# Sheet2.net
KiCad netlist of a schematic drawn in Altium Designer
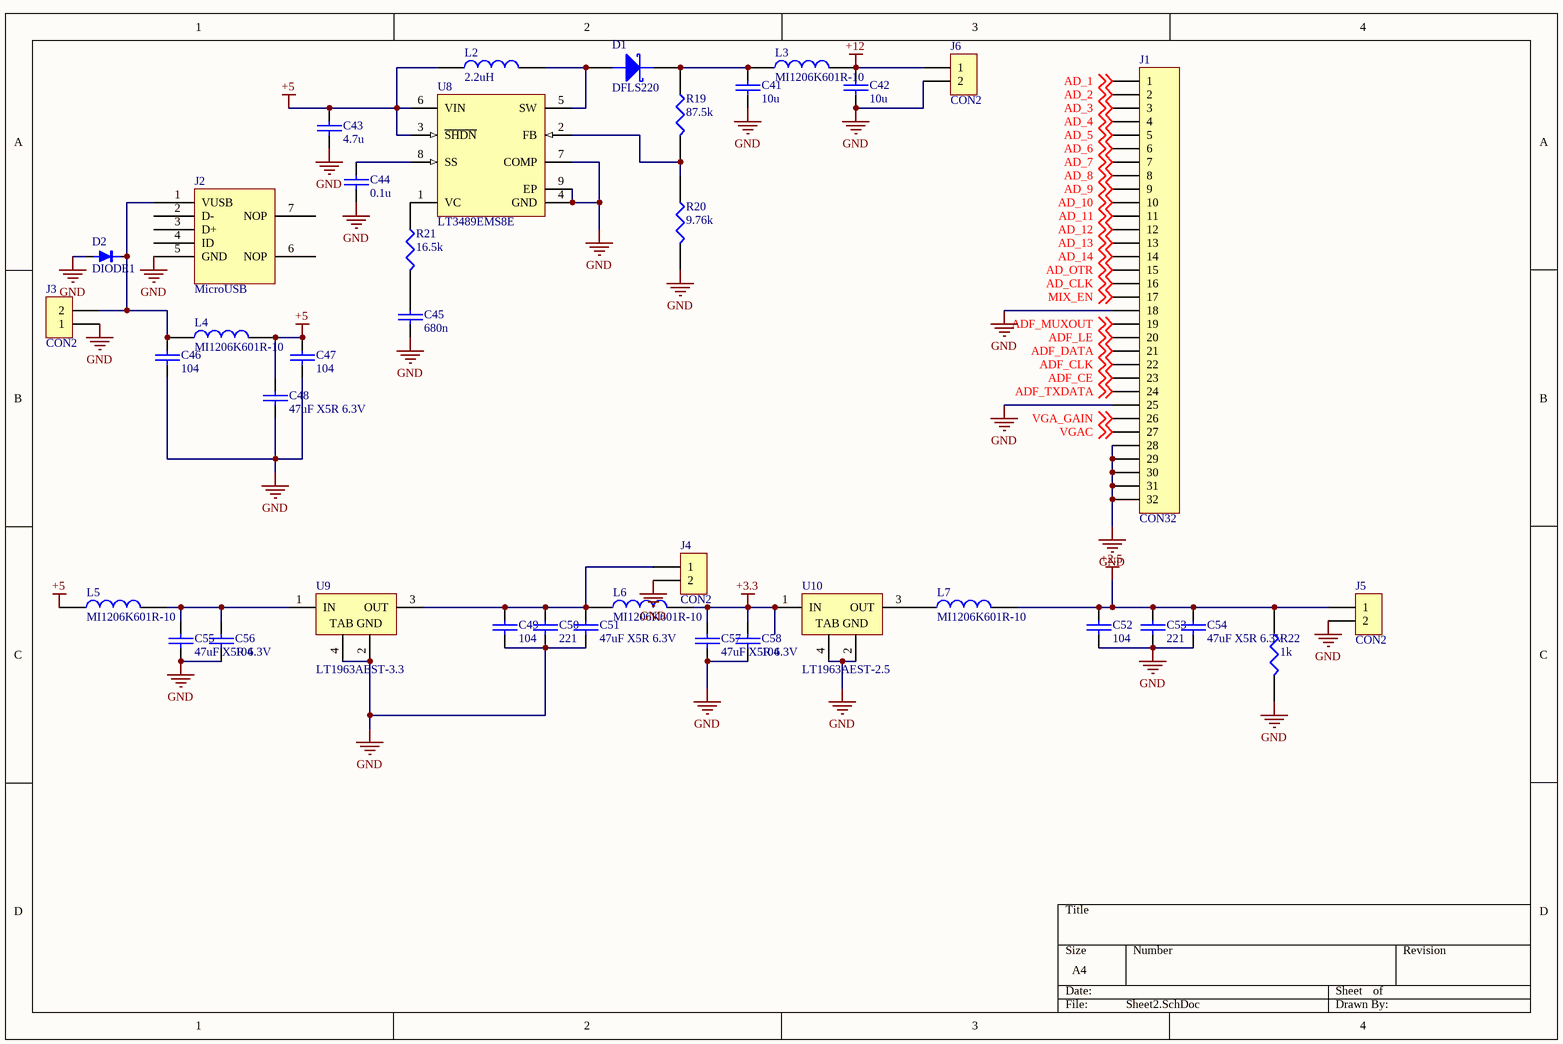
[diagram p0: Sheet2.SchDoc]

(export (version "E")
  (design (tool "Eeschema 10.0.6"))
  (components
    (comp (ref "C41")
      (value "10u")
      (footprint "0603_R")
      (description "Capacitor")
      (libsource (lib "Miscellaneous Devices") (part "CAP"))
    )
    (comp (ref "C42")
      (value "10u")
      (footprint "0603_R")
      (description "Capacitor")
      (libsource (lib "Miscellaneous Devices") (part "CAP"))
    )
    (comp (ref "C43")
      (value "4.7u")
      (footprint "0603_R")
      (description "Capacitor")
      (libsource (lib "Miscellaneous Devices") (part "CAP"))
    )
    (comp (ref "C44")
      (value "0.1u")
      (footprint "0603_R")
      (description "Capacitor")
      (libsource (lib "Miscellaneous Devices") (part "CAP"))
    )
    (comp (ref "C45")
      (value "680n")
      (footprint "0603_R")
      (description "Capacitor")
      (libsource (lib "Miscellaneous Devices") (part "CAP"))
    )
    (comp (ref "C46")
      (value "104")
      (footprint "0603_C")
      (description "Capacitor")
      (libsource (lib "Miscellaneous Devices") (part "CAP"))
    )
    (comp (ref "C47")
      (value "104")
      (footprint "0603_C")
      (description "Capacitor")
      (libsource (lib "Miscellaneous Devices") (part "CAP"))
    )
    (comp (ref "C48")
      (value "47uF X5R 6.3V")
      (footprint "CD2012-0805")
      (description "Capacitor")
      (libsource (lib "Miscellaneous Devices") (part "CAP"))
    )
    (comp (ref "C49")
      (value "104")
      (footprint "0603_R")
      (description "Capacitor")
      (libsource (lib "Miscellaneous Devices") (part "CAP"))
    )
    (comp (ref "C50")
      (value "221")
      (footprint "0603_R")
      (description "Capacitor")
      (libsource (lib "Miscellaneous Devices") (part "CAP"))
    )
    (comp (ref "C51")
      (value "47uF X5R 6.3V")
      (footprint "CD2012-0805")
      (description "Capacitor")
      (libsource (lib "Miscellaneous Devices") (part "CAP"))
    )
    (comp (ref "C52")
      (value "104")
      (footprint "0603_R")
      (description "Capacitor")
      (libsource (lib "Miscellaneous Devices") (part "CAP"))
    )
    (comp (ref "C53")
      (value "221")
      (footprint "0603_R")
      (description "Capacitor")
      (libsource (lib "Miscellaneous Devices") (part "CAP"))
    )
    (comp (ref "C54")
      (value "47uF X5R 6.3V")
      (footprint "CD2012-0805")
      (description "Capacitor")
      (libsource (lib "Miscellaneous Devices") (part "CAP"))
    )
    (comp (ref "C55")
      (value "47uF X5R 6.3V")
      (footprint "CD2012-0805")
      (description "Capacitor")
      (libsource (lib "Miscellaneous Devices") (part "CAP"))
    )
    (comp (ref "C56")
      (value "104")
      (footprint "0603_R")
      (description "Capacitor")
      (libsource (lib "Miscellaneous Devices") (part "CAP"))
    )
    (comp (ref "C57")
      (value "47uF X5R 6.3V")
      (footprint "CD2012-0805")
      (description "Capacitor")
      (libsource (lib "Miscellaneous Devices") (part "CAP"))
    )
    (comp (ref "C58")
      (value "104")
      (footprint "0603_R")
      (description "Capacitor")
      (libsource (lib "Miscellaneous Devices") (part "CAP"))
    )
    (comp (ref "D1")
      (value "DFLS220")
      (footprint "SOD123")
      (description "Schottky Diode")
      (libsource (lib "Miscellaneous Devices") (part "DIODE SCHOTTKY"))
    )
    (comp (ref "D2") (value "DIODE1") (footprint "DIODE0.4A") (libsource (lib "常用元件库") (part "DIODE1")))
    (comp (ref "J1")
      (value "CON32")
      (footprint "CON32")
      (description "Connector")
      (libsource (lib "Miscellaneous Devices") (part "CON32"))
    )
    (comp (ref "J2") (value "MicroUSB") (footprint "MICRO-USB") (libsource (lib "USB") (part "MicroUSB")))
    (comp (ref "J3") (value "CON2") (footprint "SIP2") (libsource (lib "常用元件库") (part "CON2")))
    (comp (ref "J4") (value "CON2") (footprint "SIP2") (libsource (lib "") (part "CON2_1")))
    (comp (ref "J5") (value "CON2") (footprint "SIP2") (libsource (lib "") (part "CON2_1")))
    (comp (ref "J6") (value "CON2") (footprint "SIP2") (libsource (lib "") (part "CON2_1")))
    (comp (ref "L2")
      (value "2.2uH")
      (footprint "CD4532-1812")
      (libsource (lib "Miscellaneous Devices") (part "INDUCTOR"))
    )
    (comp (ref "L3")
      (value "MI1206K601R-10")
      (footprint "1206")
      (libsource (lib "Miscellaneous Devices") (part "INDUCTOR"))
    )
    (comp (ref "L4")
      (value "MI1206K601R-10")
      (footprint "1206")
      (libsource (lib "Miscellaneous Devices") (part "INDUCTOR"))
    )
    (comp (ref "L5")
      (value "MI1206K601R-10")
      (footprint "1206")
      (libsource (lib "Miscellaneous Devices") (part "INDUCTOR"))
    )
    (comp (ref "L6")
      (value "MI1206K601R-10")
      (footprint "1206")
      (libsource (lib "Miscellaneous Devices") (part "INDUCTOR"))
    )
    (comp (ref "L7")
      (value "MI1206K601R-10")
      (footprint "1206")
      (libsource (lib "Miscellaneous Devices") (part "INDUCTOR"))
    )
    (comp (ref "R19")
      (value "87.5k")
      (footprint "0603_R")
      (libsource (lib "Miscellaneous Devices") (part "RES1"))
    )
    (comp (ref "R20")
      (value "9.76k")
      (footprint "0603_R")
      (libsource (lib "Miscellaneous Devices") (part "RES1"))
    )
    (comp (ref "R21")
      (value "16.5k")
      (footprint "0603_R")
      (libsource (lib "Miscellaneous Devices") (part "RES1"))
    )
    (comp (ref "R22")
      (value "1k")
      (footprint "0603_R")
      (libsource (lib "Miscellaneous Devices") (part "RES1"))
    )
    (comp (ref "U8")
      (value "LT3489EMS8E")
      (footprint "LT-MS8E-8-2060X1830TP_N")
      (description "2 MHz Boost DC/DC Converter with 2.5 A Switch and Soft-Start, 8-pin SOP (MS8E-8), -40 to 85 degC")
      (fields (field (name "MANUFACTURER") "Linear Technology"))
      (libsource (lib "Linear Technology Power Management Switching Regulator LT1074-LT8705") (part "LT3489EMS8E"))
    )
    (comp (ref "U9")
      (value "LT1963AEST-3.3")
      (footprint "LT-ST-3-SOT-223_N")
      (fields (field (name "MANUFACTURER") "Linear Technology"))
      (libsource (lib "Linear Technology Power Management LDO Linear Regulators") (part "LT1963AEST-3.3"))
    )
    (comp (ref "U10")
      (value "LT1963AEST-2.5")
      (footprint "LT-ST-3-SOT-223_N")
      (fields (field (name "MANUFACTURER") "Linear Technology") (field (name "PARTNUMBER") "LT1963AEST-3.3"))
      (libsource (lib "Linear Technology Power Management LDO Linear Regulators") (part "LT1963AEST-3.3"))
    )
  )
  (nets
    (net (code "1") (name "+2.5") (class "Default")
      (node (ref "C52") (pin "1") (pinfunction "1_1") (pintype "passive"))
      (node (ref "C53") (pin "1") (pinfunction "1_1") (pintype "passive"))
      (node (ref "C54") (pin "1") (pinfunction "1_1") (pintype "passive"))
      (node (ref "J5") (pin "1") (pinfunction "1_1") (pintype "passive"))
      (node (ref "L7") (pin "2") (pinfunction "2_2") (pintype "passive"))
      (node (ref "R22") (pin "1") (pinfunction "1_1") (pintype "passive"))
    )
    (net (code "2") (name "+3.3") (class "Default")
      (node (ref "C57") (pin "1") (pinfunction "1_1") (pintype "passive"))
      (node (ref "C58") (pin "1") (pinfunction "1_1") (pintype "passive"))
      (node (ref "L6") (pin "2") (pinfunction "2_2") (pintype "passive"))
      (node (ref "U10") (pin "1") (pinfunction "IN_1") (pintype "power_in"))
    )
    (net (code "3") (name "+5") (class "Default")
      (node (ref "C43") (pin "1") (pinfunction "1_1") (pintype "passive"))
      (node (ref "C47") (pin "1") (pinfunction "1_1") (pintype "passive"))
      (node (ref "C48") (pin "1") (pinfunction "1_1") (pintype "passive"))
      (node (ref "L2") (pin "1") (pinfunction "1_1") (pintype "passive"))
      (node (ref "L4") (pin "2") (pinfunction "2_2") (pintype "passive"))
      (node (ref "L5") (pin "1") (pinfunction "1_1") (pintype "passive"))
      (node (ref "U8") (pin "3") (pinfunction "~{SHDN}_3") (pintype "input"))
      (node (ref "U8") (pin "6") (pinfunction "VIN_6") (pintype "power_in"))
    )
    (net (code "4") (name "+12") (class "Default")
      (node (ref "C42") (pin "1") (pinfunction "1_1") (pintype "passive"))
      (node (ref "J6") (pin "1") (pinfunction "1_1") (pintype "passive"))
      (node (ref "L3") (pin "2") (pinfunction "2_2") (pintype "passive"))
    )
    (net (code "5") (name "ADF_CE") (class "Default")
      (node (ref "J1") (pin "23") (pinfunction "23_23") (pintype "passive"))
    )
    (net (code "6") (name "ADF_CLK") (class "Default")
      (node (ref "J1") (pin "22") (pinfunction "22_22") (pintype "passive"))
    )
    (net (code "7") (name "ADF_DATA") (class "Default")
      (node (ref "J1") (pin "21") (pinfunction "21_21") (pintype "passive"))
    )
    (net (code "8") (name "ADF_LE") (class "Default")
      (node (ref "J1") (pin "20") (pinfunction "20_20") (pintype "passive"))
    )
    (net (code "9") (name "ADF_MUXOUT") (class "Default")
      (node (ref "J1") (pin "19") (pinfunction "19_19") (pintype "passive"))
    )
    (net (code "10") (name "ADF_TXDATA") (class "Default")
      (node (ref "J1") (pin "24") (pinfunction "24_24") (pintype "passive"))
    )
    (net (code "11") (name "AD_1") (class "Default")
      (node (ref "J1") (pin "1") (pinfunction "1_1") (pintype "passive"))
    )
    (net (code "12") (name "AD_2") (class "Default")
      (node (ref "J1") (pin "2") (pinfunction "2_2") (pintype "passive"))
    )
    (net (code "13") (name "AD_3") (class "Default")
      (node (ref "J1") (pin "3") (pinfunction "3_3") (pintype "passive"))
    )
    (net (code "14") (name "AD_4") (class "Default")
      (node (ref "J1") (pin "4") (pinfunction "4_4") (pintype "passive"))
    )
    (net (code "15") (name "AD_5") (class "Default")
      (node (ref "J1") (pin "5") (pinfunction "5_5") (pintype "passive"))
    )
    (net (code "16") (name "AD_6") (class "Default")
      (node (ref "J1") (pin "6") (pinfunction "6_6") (pintype "passive"))
    )
    (net (code "17") (name "AD_7") (class "Default")
      (node (ref "J1") (pin "7") (pinfunction "7_7") (pintype "passive"))
    )
    (net (code "18") (name "AD_8") (class "Default")
      (node (ref "J1") (pin "8") (pinfunction "8_8") (pintype "passive"))
    )
    (net (code "19") (name "AD_9") (class "Default")
      (node (ref "J1") (pin "9") (pinfunction "9_9") (pintype "passive"))
    )
    (net (code "20") (name "AD_10") (class "Default")
      (node (ref "J1") (pin "10") (pinfunction "10_10") (pintype "passive"))
    )
    (net (code "21") (name "AD_11") (class "Default")
      (node (ref "J1") (pin "11") (pinfunction "11_11") (pintype "passive"))
    )
    (net (code "22") (name "AD_12") (class "Default")
      (node (ref "J1") (pin "12") (pinfunction "12_12") (pintype "passive"))
    )
    (net (code "23") (name "AD_13") (class "Default")
      (node (ref "J1") (pin "13") (pinfunction "13_13") (pintype "passive"))
    )
    (net (code "24") (name "AD_14") (class "Default")
      (node (ref "J1") (pin "14") (pinfunction "14_14") (pintype "passive"))
    )
    (net (code "25") (name "AD_CLK") (class "Default")
      (node (ref "J1") (pin "16") (pinfunction "16_16") (pintype "passive"))
    )
    (net (code "26") (name "AD_OTR") (class "Default")
      (node (ref "J1") (pin "15") (pinfunction "15_15") (pintype "passive"))
    )
    (net (code "27") (name "GND") (class "Default")
      (node (ref "C41") (pin "2") (pinfunction "2_2") (pintype "passive"))
      (node (ref "C42") (pin "2") (pinfunction "2_2") (pintype "passive"))
      (node (ref "C43") (pin "2") (pinfunction "2_2") (pintype "passive"))
      (node (ref "C44") (pin "2") (pinfunction "2_2") (pintype "passive"))
      (node (ref "C45") (pin "2") (pinfunction "2_2") (pintype "passive"))
      (node (ref "C46") (pin "2") (pinfunction "2_2") (pintype "passive"))
      (node (ref "C47") (pin "2") (pinfunction "2_2") (pintype "passive"))
      (node (ref "C48") (pin "2") (pinfunction "2_2") (pintype "passive"))
      (node (ref "C49") (pin "2") (pinfunction "2_2") (pintype "passive"))
      (node (ref "C50") (pin "2") (pinfunction "2_2") (pintype "passive"))
      (node (ref "C51") (pin "2") (pinfunction "2_2") (pintype "passive"))
      (node (ref "C52") (pin "2") (pinfunction "2_2") (pintype "passive"))
      (node (ref "C53") (pin "2") (pinfunction "2_2") (pintype "passive"))
      (node (ref "C54") (pin "2") (pinfunction "2_2") (pintype "passive"))
      (node (ref "C55") (pin "2") (pinfunction "2_2") (pintype "passive"))
      (node (ref "C56") (pin "2") (pinfunction "2_2") (pintype "passive"))
      (node (ref "C57") (pin "2") (pinfunction "2_2") (pintype "passive"))
      (node (ref "C58") (pin "2") (pinfunction "2_2") (pintype "passive"))
      (node (ref "D2") (pin "A") (pinfunction "A_A") (pintype "passive"))
      (node (ref "J1") (pin "18") (pinfunction "18_18") (pintype "passive"))
      (node (ref "J1") (pin "25") (pinfunction "25_25") (pintype "passive"))
      (node (ref "J1") (pin "28") (pinfunction "28_28") (pintype "passive"))
      (node (ref "J1") (pin "29") (pinfunction "29_29") (pintype "passive"))
      (node (ref "J1") (pin "30") (pinfunction "30_30") (pintype "passive"))
      (node (ref "J1") (pin "31") (pinfunction "31_31") (pintype "passive"))
      (node (ref "J1") (pin "32") (pinfunction "32_32") (pintype "passive"))
      (node (ref "J2") (pin "5") (pinfunction "GND_5") (pintype "passive"))
      (node (ref "J3") (pin "1") (pinfunction "1_1") (pintype "passive"))
      (node (ref "J4") (pin "2") (pinfunction "2_2") (pintype "passive"))
      (node (ref "J5") (pin "2") (pinfunction "2_2") (pintype "passive"))
      (node (ref "J6") (pin "2") (pinfunction "2_2") (pintype "passive"))
      (node (ref "R20") (pin "2") (pinfunction "2_2") (pintype "passive"))
      (node (ref "R22") (pin "2") (pinfunction "2_2") (pintype "passive"))
      (node (ref "U10") (pin "2") (pinfunction "GND_2") (pintype "power_in"))
      (node (ref "U10") (pin "4") (pinfunction "TAB_4") (pintype "power_in"))
      (node (ref "U8") (pin "4") (pinfunction "GND_4") (pintype "power_in"))
      (node (ref "U8") (pin "7") (pinfunction "COMP_7") (pintype "passive"))
      (node (ref "U8") (pin "9") (pinfunction "EP_9") (pintype "power_in"))
      (node (ref "U9") (pin "2") (pinfunction "GND_2") (pintype "power_in"))
      (node (ref "U9") (pin "4") (pinfunction "TAB_4") (pintype "power_in"))
    )
    (net (code "28") (name "MIX_EN") (class "Default")
      (node (ref "J1") (pin "17") (pinfunction "17_17") (pintype "passive"))
    )
    (net (code "29") (name "Net-(C45-Pad1)") (class "Default")
      (node (ref "C45") (pin "1") (pinfunction "1_1") (pintype "passive"))
      (node (ref "R21") (pin "2") (pinfunction "2_2") (pintype "passive"))
    )
    (net (code "30") (name "Net-(D1-A)") (class "Default")
      (node (ref "D1") (pin "1") (pinfunction "A_1") (pintype "passive"))
      (node (ref "L2") (pin "2") (pinfunction "2_2") (pintype "passive"))
      (node (ref "U8") (pin "5") (pinfunction "SW_5") (pintype "power_in"))
    )
    (net (code "31") (name "Net-(D1-K)") (class "Default")
      (node (ref "C41") (pin "1") (pinfunction "1_1") (pintype "passive"))
      (node (ref "D1") (pin "2") (pinfunction "K_2") (pintype "passive"))
      (node (ref "L3") (pin "1") (pinfunction "1_1") (pintype "passive"))
      (node (ref "R19") (pin "1") (pinfunction "1_1") (pintype "passive"))
    )
    (net (code "32") (name "Net-(J2-VUSB)") (class "Default")
      (node (ref "C46") (pin "1") (pinfunction "1_1") (pintype "passive"))
      (node (ref "D2") (pin "K") (pinfunction "K_K") (pintype "passive"))
      (node (ref "J2") (pin "1") (pinfunction "VUSB_1") (pintype "passive"))
      (node (ref "J3") (pin "2") (pinfunction "2_2") (pintype "passive"))
      (node (ref "L4") (pin "1") (pinfunction "1_1") (pintype "passive"))
    )
    (net (code "33") (name "Net-(U8-FB)") (class "Default")
      (node (ref "R19") (pin "2") (pinfunction "2_2") (pintype "passive"))
      (node (ref "R20") (pin "1") (pinfunction "1_1") (pintype "passive"))
      (node (ref "U8") (pin "2") (pinfunction "FB_2") (pintype "input"))
    )
    (net (code "34") (name "Net-(U8-SS)") (class "Default")
      (node (ref "C44") (pin "1") (pinfunction "1_1") (pintype "passive"))
      (node (ref "U8") (pin "8") (pinfunction "SS_8") (pintype "input"))
    )
    (net (code "35") (name "Net-(U8-VC)") (class "Default")
      (node (ref "R21") (pin "1") (pinfunction "1_1") (pintype "passive"))
      (node (ref "U8") (pin "1") (pinfunction "VC_1") (pintype "passive"))
    )
    (net (code "36") (name "Net-(U9-IN)") (class "Default")
      (node (ref "C55") (pin "1") (pinfunction "1_1") (pintype "passive"))
      (node (ref "C56") (pin "1") (pinfunction "1_1") (pintype "passive"))
      (node (ref "L5") (pin "2") (pinfunction "2_2") (pintype "passive"))
      (node (ref "U9") (pin "1") (pinfunction "IN_1") (pintype "power_in"))
    )
    (net (code "37") (name "Net-(U9-OUT)") (class "Default")
      (node (ref "C49") (pin "1") (pinfunction "1_1") (pintype "passive"))
      (node (ref "C50") (pin "1") (pinfunction "1_1") (pintype "passive"))
      (node (ref "C51") (pin "1") (pinfunction "1_1") (pintype "passive"))
      (node (ref "J4") (pin "1") (pinfunction "1_1") (pintype "passive"))
      (node (ref "L6") (pin "1") (pinfunction "1_1") (pintype "passive"))
      (node (ref "U9") (pin "3") (pinfunction "OUT_3") (pintype "power_in"))
    )
    (net (code "38") (name "Net-(U10-OUT)") (class "Default")
      (node (ref "L7") (pin "1") (pinfunction "1_1") (pintype "passive"))
      (node (ref "U10") (pin "3") (pinfunction "OUT_3") (pintype "power_in"))
    )
    (net (code "39") (name "VGAC") (class "Default")
      (node (ref "J1") (pin "27") (pinfunction "27_27") (pintype "passive"))
    )
    (net (code "40") (name "VGA_GAIN") (class "Default")
      (node (ref "J1") (pin "26") (pinfunction "26_26") (pintype "passive"))
    )
    (net (code "41") (name "unconnected-(J2-D+-Pad3)") (class "Default")
      (node (ref "J2") (pin "3") (pinfunction "D+_3") (pintype "passive"))
    )
    (net (code "42") (name "unconnected-(J2-D--Pad2)") (class "Default")
      (node (ref "J2") (pin "2") (pinfunction "D-_2") (pintype "passive"))
    )
    (net (code "43") (name "unconnected-(J2-ID-Pad4)") (class "Default")
      (node (ref "J2") (pin "4") (pinfunction "ID_4") (pintype "passive"))
    )
    (net (code "44") (name "unconnected-(J2-NOP-Pad6)") (class "Default")
      (node (ref "J2") (pin "6") (pinfunction "NOP_6") (pintype "passive"))
    )
    (net (code "45") (name "unconnected-(J2-NOP-Pad7)") (class "Default")
      (node (ref "J2") (pin "7") (pinfunction "NOP_7") (pintype "passive"))
    )
  )
)
